# Krzysztof_Molski.net
KiCad netlist of a schematic drawn in EAGLE
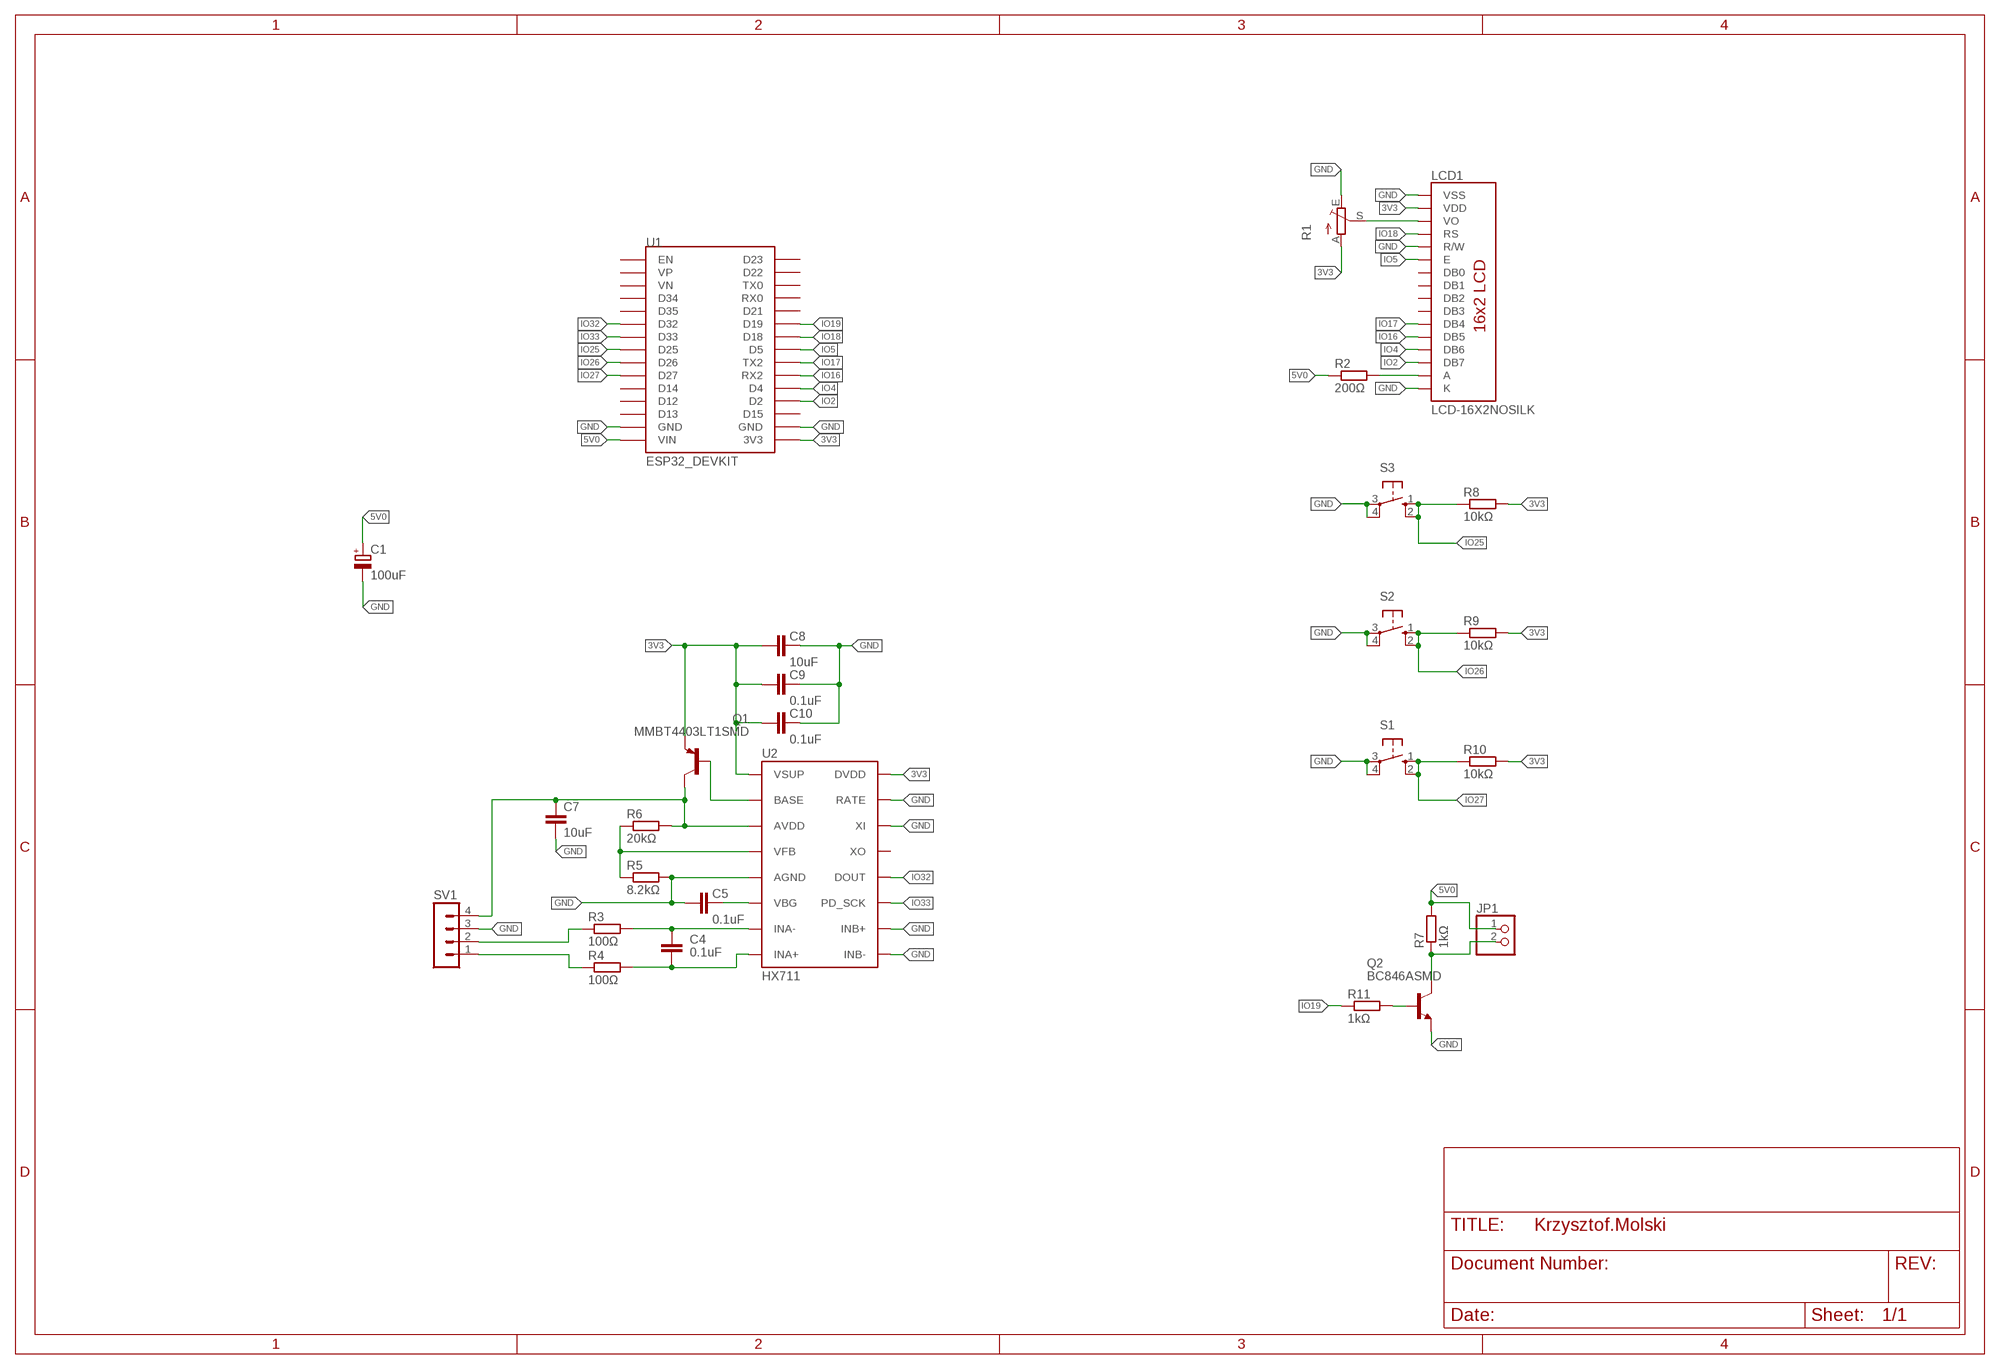
[diagram p0: schematic, sheet 1]

(export (version "E")
  (design (tool "Eeschema 10.0.6"))
  (components
    (comp (ref "C1")
      (value "100uF")
      (footprint "eagle-import:CT3528")
      (libsource (lib "eagle-import") (part "CPOL-EUCT3528"))
    )
    (comp (ref "C4")
      (value "0.1uF")
      (footprint "eagle-import:C1206")
      (libsource (lib "eagle-import") (part "C-EUC1206"))
    )
    (comp (ref "C5")
      (value "0.1uF")
      (footprint "eagle-import:C1206")
      (libsource (lib "eagle-import") (part "C-EUC1206"))
    )
    (comp (ref "C7")
      (value "10uF")
      (footprint "eagle-import:C1206")
      (libsource (lib "eagle-import") (part "C-EUC1206"))
    )
    (comp (ref "C8")
      (value "10uF")
      (footprint "eagle-import:C1206")
      (libsource (lib "eagle-import") (part "C-EUC1206"))
    )
    (comp (ref "C9")
      (value "0.1uF")
      (footprint "eagle-import:C1206")
      (libsource (lib "eagle-import") (part "C-EUC1206"))
    )
    (comp (ref "C10")
      (value "0.1uF")
      (footprint "eagle-import:C1206")
      (libsource (lib "eagle-import") (part "C-EUC1206"))
    )
    (comp (ref "JP1")
      (value "PINHD-1X2")
      (footprint "eagle-import:1X02")
      (libsource (lib "eagle-import") (part "PINHD-1X2"))
    )
    (comp (ref "LCD1")
      (value "LCD-16X2NOSILK")
      (footprint "eagle-import:LCD-16X2_NOSILK")
      (libsource (lib "eagle-import") (part "LCD-16X2NOSILK"))
    )
    (comp (ref "Q1")
      (value "MMBT4403LT1SMD")
      (footprint "eagle-import:SOT23-BEC")
      (libsource (lib "eagle-import") (part "MMBT4403SMDLT1"))
    )
    (comp (ref "Q2")
      (value "BC846ASMD")
      (footprint "eagle-import:SOT23")
      (libsource (lib "eagle-import") (part "BC846SMDA"))
    )
    (comp (ref "R1")
      (value "TRIM_EU-CA6V")
      (footprint "eagle-import:CA6V")
      (libsource (lib "eagle-import") (part "TRIM_EU-CA6V"))
    )
    (comp (ref "R2")
      (value "200Ω")
      (footprint "eagle-import:R0805")
      (libsource (lib "eagle-import") (part "R-EU_R0805"))
    )
    (comp (ref "R3")
      (value "100Ω")
      (footprint "eagle-import:R0805")
      (libsource (lib "eagle-import") (part "R-EU_R0805"))
    )
    (comp (ref "R4")
      (value "100Ω")
      (footprint "eagle-import:R0805")
      (libsource (lib "eagle-import") (part "R-EU_R0805"))
    )
    (comp (ref "R5")
      (value "8.2kΩ")
      (footprint "eagle-import:R0805")
      (libsource (lib "eagle-import") (part "R-EU_R0805"))
    )
    (comp (ref "R6")
      (value "20kΩ")
      (footprint "eagle-import:R0805")
      (libsource (lib "eagle-import") (part "R-EU_R0805"))
    )
    (comp (ref "R7")
      (value "1kΩ")
      (footprint "eagle-import:R0805")
      (libsource (lib "eagle-import") (part "R-EU_R0805"))
    )
    (comp (ref "R8")
      (value "10kΩ")
      (footprint "eagle-import:R0805")
      (libsource (lib "eagle-import") (part "R-EU_R0805"))
    )
    (comp (ref "R9")
      (value "10kΩ")
      (footprint "eagle-import:R0805")
      (libsource (lib "eagle-import") (part "R-EU_R0805"))
    )
    (comp (ref "R10")
      (value "10kΩ")
      (footprint "eagle-import:R0805")
      (libsource (lib "eagle-import") (part "R-EU_R0805"))
    )
    (comp (ref "R11")
      (value "1kΩ")
      (footprint "eagle-import:R0805")
      (libsource (lib "eagle-import") (part "R-EU_R0805"))
    )
    (comp (ref "S1")
      (value "10-XX")
      (footprint "eagle-import:B3F-10XX")
      (fields (field (name "MPN") "B3F-1000"))
      (libsource (lib "eagle-import") (part "10-XX"))
    )
    (comp (ref "S2")
      (value "10-XX")
      (footprint "eagle-import:B3F-10XX")
      (fields (field (name "MPN") "B3F-1000"))
      (libsource (lib "eagle-import") (part "10-XX"))
    )
    (comp (ref "S3")
      (value "10-XX")
      (footprint "eagle-import:B3F-10XX")
      (fields (field (name "MPN") "B3F-1000"))
      (libsource (lib "eagle-import") (part "10-XX"))
    )
    (comp (ref "SV1")
      (value "MA04-1")
      (footprint "eagle-import:MA04-1")
      (libsource (lib "eagle-import") (part "MA04-1"))
    )
    (comp (ref "U1")
      (value "ESP32_DEVKIT")
      (footprint "eagle-import:ESP32_DEVKIT")
      (libsource (lib "eagle-import") (part "ESP32_DEVKIT"))
    )
    (comp (ref "U2")
      (value "HX711")
      (footprint "eagle-import:SO16")
      (libsource (lib "eagle-import") (part "HX711"))
    )
  )
  (nets
    (net (code "1") (name "3V3") (class "Default")
      (node (ref "C10") (pin "2") (pinfunction "2_2") (pintype "passive"))
      (node (ref "C8") (pin "2") (pinfunction "2_2") (pintype "passive"))
      (node (ref "C9") (pin "2") (pinfunction "2_2") (pintype "passive"))
      (node (ref "LCD1") (pin "2") (pinfunction "VDD_2") (pintype "power_in"))
      (node (ref "Q1") (pin "E") (pinfunction "E_E") (pintype "passive"))
      (node (ref "R1") (pin "A") (pinfunction "A_A") (pintype "passive"))
      (node (ref "R10") (pin "2") (pinfunction "2_2") (pintype "passive"))
      (node (ref "R8") (pin "2") (pinfunction "2_2") (pintype "passive"))
      (node (ref "R9") (pin "2") (pinfunction "2_2") (pintype "passive"))
      (node (ref "U1") (pin "3V3") (pinfunction "3V3_3V3") (pintype "bidirectional"))
      (node (ref "U2") (pin "1") (pinfunction "VSUP_1") (pintype "bidirectional"))
      (node (ref "U2") (pin "16") (pinfunction "DVDD_16") (pintype "bidirectional"))
    )
    (net (code "2") (name "5V0") (class "Default")
      (node (ref "C1") (pin "+") (pinfunction "+_+") (pintype "passive"))
      (node (ref "JP1") (pin "1") (pinfunction "1_1") (pintype "passive"))
      (node (ref "R2") (pin "1") (pinfunction "1_1") (pintype "passive"))
      (node (ref "R7") (pin "2") (pinfunction "2_2") (pintype "passive"))
      (node (ref "U1") (pin "VIN") (pinfunction "VIN_VIN") (pintype "bidirectional"))
    )
    (net (code "3") (name "GND") (class "Default")
      (node (ref "C1") (pin "-") (pinfunction "-_-") (pintype "passive"))
      (node (ref "C10") (pin "1") (pinfunction "1_1") (pintype "passive"))
      (node (ref "C5") (pin "2") (pinfunction "2_2") (pintype "passive"))
      (node (ref "C7") (pin "2") (pinfunction "2_2") (pintype "passive"))
      (node (ref "C8") (pin "1") (pinfunction "1_1") (pintype "passive"))
      (node (ref "C9") (pin "1") (pinfunction "1_1") (pintype "passive"))
      (node (ref "LCD1") (pin "1") (pinfunction "VSS_1") (pintype "power_in"))
      (node (ref "LCD1") (pin "16") (pinfunction "K_16") (pintype "power_in"))
      (node (ref "LCD1") (pin "5") (pinfunction "R/W_5") (pintype "input"))
      (node (ref "Q2") (pin "2") (pinfunction "E_2") (pintype "passive"))
      (node (ref "R1") (pin "E") (pinfunction "E_E") (pintype "passive"))
      (node (ref "R5") (pin "2") (pinfunction "2_2") (pintype "passive"))
      (node (ref "S1") (pin "3") (pinfunction "P_3") (pintype "passive"))
      (node (ref "S1") (pin "4") (pinfunction "P1_4") (pintype "passive"))
      (node (ref "S2") (pin "3") (pinfunction "P_3") (pintype "passive"))
      (node (ref "S2") (pin "4") (pinfunction "P1_4") (pintype "passive"))
      (node (ref "S3") (pin "3") (pinfunction "P_3") (pintype "passive"))
      (node (ref "S3") (pin "4") (pinfunction "P1_4") (pintype "passive"))
      (node (ref "SV1") (pin "3") (pinfunction "3_3") (pintype "passive"))
      (node (ref "U1") (pin "GND@1") (pinfunction "GND_GND@1") (pintype "bidirectional"))
      (node (ref "U1") (pin "GND@2") (pinfunction "GND_GND@2") (pintype "bidirectional"))
      (node (ref "U2") (pin "10") (pinfunction "INB+_10") (pintype "bidirectional"))
      (node (ref "U2") (pin "14") (pinfunction "XI_14") (pintype "bidirectional"))
      (node (ref "U2") (pin "15") (pinfunction "RATE_15") (pintype "bidirectional"))
      (node (ref "U2") (pin "5") (pinfunction "AGND_5") (pintype "bidirectional"))
      (node (ref "U2") (pin "9") (pinfunction "INB-_9") (pintype "bidirectional"))
    )
    (net (code "4") (name "IO2") (class "Default")
      (node (ref "LCD1") (pin "14") (pinfunction "DB7_14") (pintype "bidirectional"))
      (node (ref "U1") (pin "D2") (pinfunction "D2_D2") (pintype "bidirectional"))
    )
    (net (code "5") (name "IO4") (class "Default")
      (node (ref "LCD1") (pin "13") (pinfunction "DB6_13") (pintype "bidirectional"))
      (node (ref "U1") (pin "D4") (pinfunction "D4_D4") (pintype "bidirectional"))
    )
    (net (code "6") (name "IO5") (class "Default")
      (node (ref "LCD1") (pin "6") (pinfunction "E_6") (pintype "input"))
      (node (ref "U1") (pin "D5") (pinfunction "D5_D5") (pintype "bidirectional"))
    )
    (net (code "7") (name "IO16") (class "Default")
      (node (ref "LCD1") (pin "12") (pinfunction "DB5_12") (pintype "bidirectional"))
      (node (ref "U1") (pin "RX2") (pinfunction "RX2_RX2") (pintype "bidirectional"))
    )
    (net (code "8") (name "IO17") (class "Default")
      (node (ref "LCD1") (pin "11") (pinfunction "DB4_11") (pintype "bidirectional"))
      (node (ref "U1") (pin "TX2") (pinfunction "TX2_TX2") (pintype "bidirectional"))
    )
    (net (code "9") (name "IO18") (class "Default")
      (node (ref "LCD1") (pin "4") (pinfunction "RS_4") (pintype "input"))
      (node (ref "U1") (pin "D18") (pinfunction "D18_D18") (pintype "bidirectional"))
    )
    (net (code "10") (name "IO19") (class "Default")
      (node (ref "R11") (pin "1") (pinfunction "1_1") (pintype "passive"))
      (node (ref "U1") (pin "D19") (pinfunction "D19_D19") (pintype "bidirectional"))
    )
    (net (code "11") (name "IO25") (class "Default")
      (node (ref "R8") (pin "1") (pinfunction "1_1") (pintype "passive"))
      (node (ref "S3") (pin "1") (pinfunction "S_1") (pintype "passive"))
      (node (ref "S3") (pin "2") (pinfunction "S1_2") (pintype "passive"))
      (node (ref "U1") (pin "D25") (pinfunction "D25_D25") (pintype "bidirectional"))
    )
    (net (code "12") (name "IO26") (class "Default")
      (node (ref "R9") (pin "1") (pinfunction "1_1") (pintype "passive"))
      (node (ref "S2") (pin "1") (pinfunction "S_1") (pintype "passive"))
      (node (ref "S2") (pin "2") (pinfunction "S1_2") (pintype "passive"))
      (node (ref "U1") (pin "D26") (pinfunction "D26_D26") (pintype "bidirectional"))
    )
    (net (code "13") (name "IO27") (class "Default")
      (node (ref "R10") (pin "1") (pinfunction "1_1") (pintype "passive"))
      (node (ref "S1") (pin "1") (pinfunction "S_1") (pintype "passive"))
      (node (ref "S1") (pin "2") (pinfunction "S1_2") (pintype "passive"))
      (node (ref "U1") (pin "D27") (pinfunction "D27_D27") (pintype "bidirectional"))
    )
    (net (code "14") (name "IO32") (class "Default")
      (node (ref "U1") (pin "D32") (pinfunction "D32_D32") (pintype "bidirectional"))
      (node (ref "U2") (pin "12") (pinfunction "DOUT_12") (pintype "bidirectional"))
    )
    (net (code "15") (name "IO33") (class "Default")
      (node (ref "U1") (pin "D33") (pinfunction "D33_D33") (pintype "bidirectional"))
      (node (ref "U2") (pin "11") (pinfunction "PD_SCK_11") (pintype "bidirectional"))
    )
    (net (code "16") (name "Net-(LCD1-A)") (class "Default")
      (node (ref "LCD1") (pin "15") (pinfunction "A_15") (pintype "power_in"))
      (node (ref "R2") (pin "2") (pinfunction "2_2") (pintype "passive"))
    )
    (net (code "17") (name "Net-(LCD1-VO)") (class "Default")
      (node (ref "LCD1") (pin "3") (pinfunction "VO_3") (pintype "bidirectional"))
      (node (ref "R1") (pin "S") (pinfunction "S_S") (pintype "passive"))
    )
    (net (code "18") (name "Net-(Q2-B)") (class "Default")
      (node (ref "Q2") (pin "1") (pinfunction "B_1") (pintype "passive"))
      (node (ref "R11") (pin "2") (pinfunction "2_2") (pintype "passive"))
    )
    (net (code "19") (name "Net-(Q2-C)") (class "Default")
      (node (ref "JP1") (pin "2") (pinfunction "2_2") (pintype "passive"))
      (node (ref "Q2") (pin "3") (pinfunction "C_3") (pintype "passive"))
      (node (ref "R7") (pin "1") (pinfunction "1_1") (pintype "passive"))
    )
    (net (code "20") (name "Net-(R3-Pad1)") (class "Default")
      (node (ref "R3") (pin "1") (pinfunction "1_1") (pintype "passive"))
      (node (ref "SV1") (pin "2") (pinfunction "2_2") (pintype "passive"))
    )
    (net (code "21") (name "Net-(R4-Pad1)") (class "Default")
      (node (ref "R4") (pin "1") (pinfunction "1_1") (pintype "passive"))
      (node (ref "SV1") (pin "1") (pinfunction "1_1") (pintype "passive"))
    )
    (net (code "22") (name "Net-(U2-AVDD)") (class "Default")
      (node (ref "C7") (pin "1") (pinfunction "1_1") (pintype "passive"))
      (node (ref "Q1") (pin "C") (pinfunction "C_C") (pintype "passive"))
      (node (ref "R6") (pin "2") (pinfunction "2_2") (pintype "passive"))
      (node (ref "SV1") (pin "4") (pinfunction "4_4") (pintype "passive"))
      (node (ref "U2") (pin "3") (pinfunction "AVDD_3") (pintype "bidirectional"))
    )
    (net (code "23") (name "Net-(U2-BASE)") (class "Default")
      (node (ref "Q1") (pin "B") (pinfunction "B_B") (pintype "passive"))
      (node (ref "U2") (pin "2") (pinfunction "BASE_2") (pintype "bidirectional"))
    )
    (net (code "24") (name "Net-(U2-INA+)") (class "Default")
      (node (ref "C4") (pin "1") (pinfunction "1_1") (pintype "passive"))
      (node (ref "R4") (pin "2") (pinfunction "2_2") (pintype "passive"))
      (node (ref "U2") (pin "8") (pinfunction "INA+_8") (pintype "bidirectional"))
    )
    (net (code "25") (name "Net-(U2-INA-)") (class "Default")
      (node (ref "C4") (pin "2") (pinfunction "2_2") (pintype "passive"))
      (node (ref "R3") (pin "2") (pinfunction "2_2") (pintype "passive"))
      (node (ref "U2") (pin "7") (pinfunction "INA-_7") (pintype "bidirectional"))
    )
    (net (code "26") (name "Net-(U2-VBG)") (class "Default")
      (node (ref "C5") (pin "1") (pinfunction "1_1") (pintype "passive"))
      (node (ref "U2") (pin "6") (pinfunction "VBG_6") (pintype "bidirectional"))
    )
    (net (code "27") (name "Net-(U2-VFB)") (class "Default")
      (node (ref "R5") (pin "1") (pinfunction "1_1") (pintype "passive"))
      (node (ref "R6") (pin "1") (pinfunction "1_1") (pintype "passive"))
      (node (ref "U2") (pin "4") (pinfunction "VFB_4") (pintype "bidirectional"))
    )
    (net (code "28") (name "unconnected-(LCD1-DB0-Pad7)") (class "Default")
      (node (ref "LCD1") (pin "7") (pinfunction "DB0_7") (pintype "bidirectional"))
    )
    (net (code "29") (name "unconnected-(LCD1-DB1-Pad8)") (class "Default")
      (node (ref "LCD1") (pin "8") (pinfunction "DB1_8") (pintype "bidirectional"))
    )
    (net (code "30") (name "unconnected-(LCD1-DB2-Pad9)") (class "Default")
      (node (ref "LCD1") (pin "9") (pinfunction "DB2_9") (pintype "bidirectional"))
    )
    (net (code "31") (name "unconnected-(LCD1-DB3-Pad10)") (class "Default")
      (node (ref "LCD1") (pin "10") (pinfunction "DB3_10") (pintype "bidirectional"))
    )
    (net (code "32") (name "unconnected-(U1-PadD12)") (class "Default")
      (node (ref "U1") (pin "D12") (pinfunction "D12_D12") (pintype "bidirectional"))
    )
    (net (code "33") (name "unconnected-(U1-PadD13)") (class "Default")
      (node (ref "U1") (pin "D13") (pinfunction "D13_D13") (pintype "bidirectional"))
    )
    (net (code "34") (name "unconnected-(U1-PadD14)") (class "Default")
      (node (ref "U1") (pin "D14") (pinfunction "D14_D14") (pintype "bidirectional"))
    )
    (net (code "35") (name "unconnected-(U1-PadD15)") (class "Default")
      (node (ref "U1") (pin "D15") (pinfunction "D15_D15") (pintype "bidirectional"))
    )
    (net (code "36") (name "unconnected-(U1-PadD21)") (class "Default")
      (node (ref "U1") (pin "D21") (pinfunction "D21_D21") (pintype "bidirectional"))
    )
    (net (code "37") (name "unconnected-(U1-PadD22)") (class "Default")
      (node (ref "U1") (pin "D22") (pinfunction "D22_D22") (pintype "bidirectional"))
    )
    (net (code "38") (name "unconnected-(U1-PadD23)") (class "Default")
      (node (ref "U1") (pin "D23") (pinfunction "D23_D23") (pintype "bidirectional"))
    )
    (net (code "39") (name "unconnected-(U1-PadD34)") (class "Default")
      (node (ref "U1") (pin "D34") (pinfunction "D34_D34") (pintype "bidirectional"))
    )
    (net (code "40") (name "unconnected-(U1-PadD35)") (class "Default")
      (node (ref "U1") (pin "D35") (pinfunction "D35_D35") (pintype "bidirectional"))
    )
    (net (code "41") (name "unconnected-(U1-PadEN)") (class "Default")
      (node (ref "U1") (pin "EN") (pinfunction "EN_EN") (pintype "bidirectional"))
    )
    (net (code "42") (name "unconnected-(U1-PadRX0)") (class "Default")
      (node (ref "U1") (pin "RX0") (pinfunction "RX0_RX0") (pintype "bidirectional"))
    )
    (net (code "43") (name "unconnected-(U1-PadTX0)") (class "Default")
      (node (ref "U1") (pin "TX0") (pinfunction "TX0_TX0") (pintype "bidirectional"))
    )
    (net (code "44") (name "unconnected-(U1-PadVN)") (class "Default")
      (node (ref "U1") (pin "VN") (pinfunction "VN_VN") (pintype "bidirectional"))
    )
    (net (code "45") (name "unconnected-(U1-PadVP)") (class "Default")
      (node (ref "U1") (pin "VP") (pinfunction "VP_VP") (pintype "bidirectional"))
    )
    (net (code "46") (name "unconnected-(U2-XO-Pad13)") (class "Default")
      (node (ref "U2") (pin "13") (pinfunction "XO_13") (pintype "bidirectional"))
    )
  )
)
